# v11.net
KiCad netlist of a schematic drawn in EAGLE
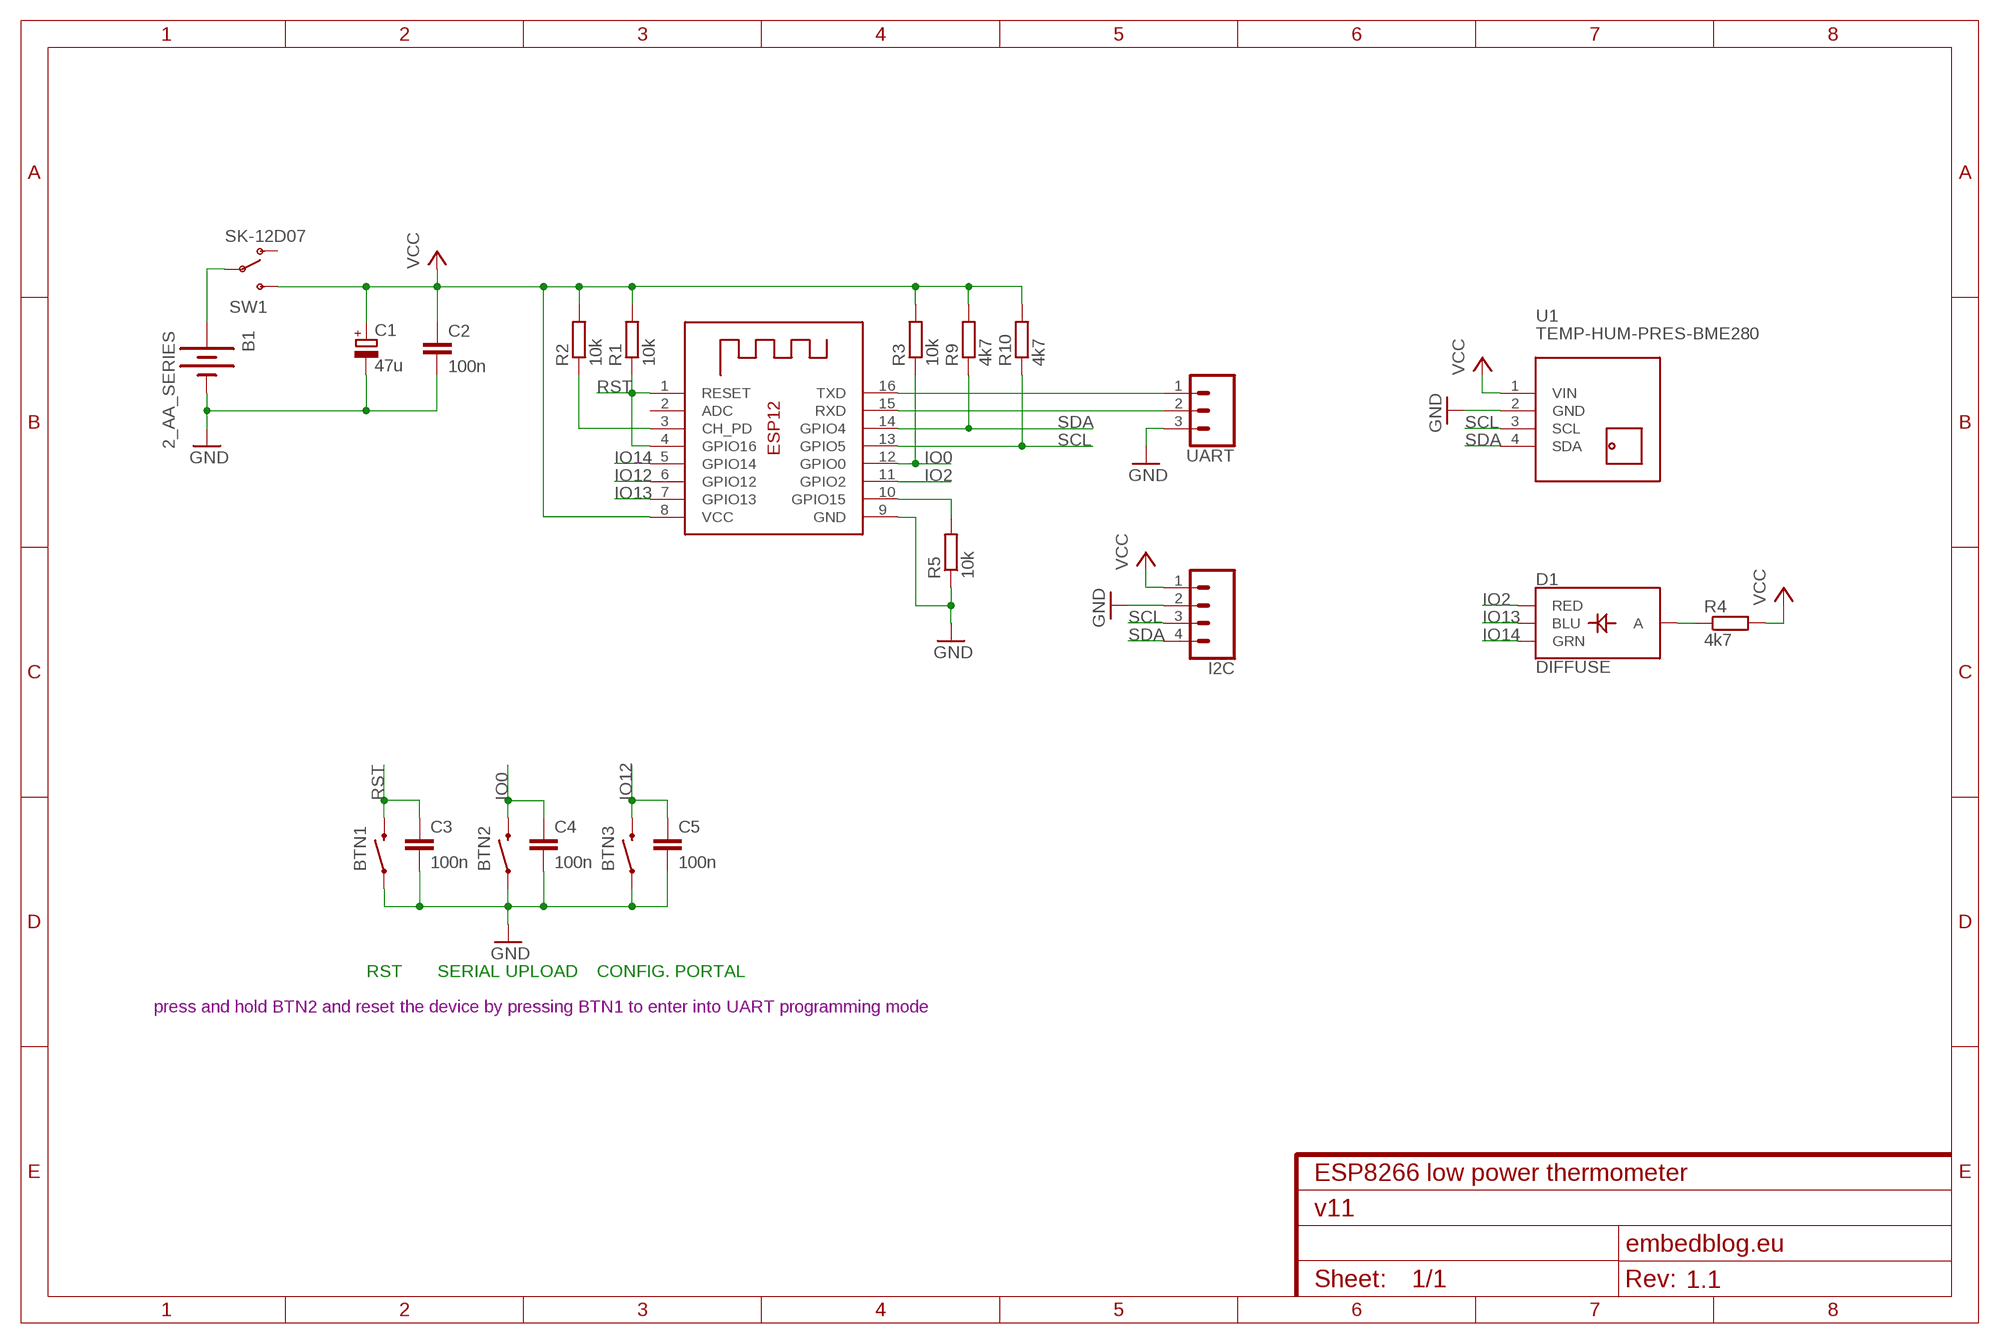
[diagram p0: schematic, sheet 1]

(export (version "E")
  (design (tool "Eeschema 10.0.6"))
  (components
    (comp (ref "B1")
      (value "2_AA_SERIES")
      (footprint "eagle-import:AA_HOLDER_BH-321-1P")
      (libsource (lib "eagle-import") (part "2_AA_SERIES"))
    )
    (comp (ref "BTN1")
      (value "MOMENTARY-SWITCH-SPST-PTH-6.0MM")
      (footprint "eagle-import:TACTILE_SWITCH_PTH_6.0MM")
      (libsource (lib "eagle-import") (part "MOMENTARY-SWITCH-SPST-PTH-6.0MM"))
    )
    (comp (ref "BTN2")
      (value "MOMENTARY-SWITCH-SPST-PTH-6.0MM")
      (footprint "eagle-import:TACTILE_SWITCH_PTH_6.0MM")
      (libsource (lib "eagle-import") (part "MOMENTARY-SWITCH-SPST-PTH-6.0MM"))
    )
    (comp (ref "BTN3")
      (value "MOMENTARY-SWITCH-SPST-PTH-6.0MM")
      (footprint "eagle-import:TACTILE_SWITCH_PTH_6.0MM")
      (libsource (lib "eagle-import") (part "MOMENTARY-SWITCH-SPST-PTH-6.0MM"))
    )
    (comp (ref "C1")
      (value "47u")
      (footprint "eagle-import:SMC_B")
      (libsource (lib "eagle-import") (part "CPOL-EUSMCB"))
    )
    (comp (ref "C2")
      (value "100n")
      (footprint "eagle-import:C1206")
      (libsource (lib "eagle-import") (part "C-EUC1206"))
    )
    (comp (ref "C3")
      (value "100n")
      (footprint "eagle-import:C1206")
      (libsource (lib "eagle-import") (part "C-EUC1206"))
    )
    (comp (ref "C4")
      (value "100n")
      (footprint "eagle-import:C1206")
      (libsource (lib "eagle-import") (part "C-EUC1206"))
    )
    (comp (ref "C5")
      (value "100n")
      (footprint "eagle-import:C1206")
      (libsource (lib "eagle-import") (part "C-EUC1206"))
    )
    (comp (ref "D1")
      (value "DIFFUSE")
      (footprint "eagle-import:LED-RGB-THRU")
      (libsource (lib "eagle-import") (part "LED-RGB-CADIFFUSE"))
    )
    (comp (ref "I2C")
      (value "CONN_04")
      (footprint "eagle-import:1X04")
      (libsource (lib "eagle-import") (part "CONN_04"))
    )
    (comp (ref "R1")
      (value "10k")
      (footprint "eagle-import:R1206")
      (libsource (lib "eagle-import") (part "R-EU_R1206"))
    )
    (comp (ref "R2")
      (value "10k")
      (footprint "eagle-import:R1206")
      (libsource (lib "eagle-import") (part "R-EU_R1206"))
    )
    (comp (ref "R3")
      (value "10k")
      (footprint "eagle-import:R1206")
      (libsource (lib "eagle-import") (part "R-EU_R1206"))
    )
    (comp (ref "R4")
      (value "4k7")
      (footprint "eagle-import:R1206")
      (libsource (lib "eagle-import") (part "R-EU_R1206"))
    )
    (comp (ref "R5")
      (value "10k")
      (footprint "eagle-import:R1206")
      (libsource (lib "eagle-import") (part "R-EU_R1206"))
    )
    (comp (ref "R9")
      (value "4k7")
      (footprint "eagle-import:R1206")
      (libsource (lib "eagle-import") (part "R-EU_R1206"))
    )
    (comp (ref "R10")
      (value "4k7")
      (footprint "eagle-import:R1206")
      (libsource (lib "eagle-import") (part "R-EU_R1206"))
    )
    (comp (ref "SW1")
      (value "SK-12D07")
      (footprint "eagle-import:SK12SWITCH")
      (libsource (lib "eagle-import") (part "SK-12D07"))
    )
    (comp (ref "U1")
      (value "TEMP-HUM-PRES-BME280")
      (footprint "eagle-import:TEMP-HUM-PRES-BME280")
      (libsource (lib "eagle-import") (part "TEMP-HUM-PRES-BME280"))
    )
    (comp (ref "UART")
      (value "455-1750-1-ND")
      (footprint "eagle-import:1X03")
      (libsource (lib "eagle-import") (part "CONN_03"))
    )
    (comp (ref "X1")
      (value "ESP-12")
      (footprint "eagle-import:ESP-12")
      (libsource (lib "eagle-import") (part "ESP-12"))
    )
  )
  (nets
    (net (code "1") (name "/IO0") (class "Default")
      (node (ref "BTN2") (pin "3") (pinfunction "2_3") (pintype "passive"))
      (node (ref "C4") (pin "1") (pinfunction "1_1") (pintype "passive"))
      (node (ref "R3") (pin "1") (pinfunction "1_1") (pintype "passive"))
      (node (ref "X1") (pin "12") (pinfunction "GPIO0_12") (pintype "bidirectional"))
    )
    (net (code "2") (name "/IO2") (class "Default")
      (node (ref "D1") (pin "1") (pinfunction "RED_1") (pintype "bidirectional"))
      (node (ref "X1") (pin "11") (pinfunction "GPIO2_11") (pintype "bidirectional"))
    )
    (net (code "3") (name "/IO12") (class "Default")
      (node (ref "BTN3") (pin "3") (pinfunction "2_3") (pintype "passive"))
      (node (ref "C5") (pin "1") (pinfunction "1_1") (pintype "passive"))
      (node (ref "X1") (pin "6") (pinfunction "GPIO12_6") (pintype "bidirectional"))
    )
    (net (code "4") (name "/IO13") (class "Default")
      (node (ref "D1") (pin "4") (pinfunction "BLU_4") (pintype "bidirectional"))
      (node (ref "X1") (pin "7") (pinfunction "GPIO13_7") (pintype "bidirectional"))
    )
    (net (code "5") (name "/IO14") (class "Default")
      (node (ref "D1") (pin "3") (pinfunction "GRN_3") (pintype "bidirectional"))
      (node (ref "X1") (pin "5") (pinfunction "GPIO14_5") (pintype "bidirectional"))
    )
    (net (code "6") (name "/RST") (class "Default")
      (node (ref "BTN1") (pin "3") (pinfunction "2_3") (pintype "passive"))
      (node (ref "C3") (pin "1") (pinfunction "1_1") (pintype "passive"))
      (node (ref "R1") (pin "1") (pinfunction "1_1") (pintype "passive"))
      (node (ref "X1") (pin "1") (pinfunction "RESET_1") (pintype "input"))
      (node (ref "X1") (pin "4") (pinfunction "GPIO16_4") (pintype "bidirectional"))
    )
    (net (code "7") (name "/SCL") (class "Default")
      (node (ref "I2C") (pin "3") (pinfunction "3_3") (pintype "passive"))
      (node (ref "R10") (pin "1") (pinfunction "1_1") (pintype "passive"))
      (node (ref "U1") (pin "3") (pinfunction "SCL_3") (pintype "bidirectional"))
      (node (ref "X1") (pin "13") (pinfunction "GPIO5_13") (pintype "bidirectional"))
    )
    (net (code "8") (name "/SDA") (class "Default")
      (node (ref "I2C") (pin "4") (pinfunction "4_4") (pintype "passive"))
      (node (ref "R9") (pin "1") (pinfunction "1_1") (pintype "passive"))
      (node (ref "U1") (pin "4") (pinfunction "SDA_4") (pintype "bidirectional"))
      (node (ref "X1") (pin "14") (pinfunction "GPIO4_14") (pintype "bidirectional"))
    )
    (net (code "9") (name "GND") (class "Default")
      (node (ref "B1") (pin "NEG") (pinfunction "-_NEG") (pintype "power_in"))
      (node (ref "BTN1") (pin "1") (pinfunction "1_1") (pintype "passive"))
      (node (ref "BTN2") (pin "1") (pinfunction "1_1") (pintype "passive"))
      (node (ref "BTN3") (pin "1") (pinfunction "1_1") (pintype "passive"))
      (node (ref "C1") (pin "-") (pinfunction "-_-") (pintype "passive"))
      (node (ref "C2") (pin "2") (pinfunction "2_2") (pintype "passive"))
      (node (ref "C3") (pin "2") (pinfunction "2_2") (pintype "passive"))
      (node (ref "C4") (pin "2") (pinfunction "2_2") (pintype "passive"))
      (node (ref "C5") (pin "2") (pinfunction "2_2") (pintype "passive"))
      (node (ref "I2C") (pin "2") (pinfunction "2_2") (pintype "passive"))
      (node (ref "R5") (pin "1") (pinfunction "1_1") (pintype "passive"))
      (node (ref "U1") (pin "2") (pinfunction "GND_2") (pintype "power_in"))
      (node (ref "UART") (pin "3") (pinfunction "3_3") (pintype "passive"))
      (node (ref "X1") (pin "9") (pinfunction "GND_9") (pintype "power_in"))
    )
    (net (code "10") (name "Net-(B1-+)") (class "Default")
      (node (ref "B1") (pin "POS") (pinfunction "+_POS") (pintype "power_in"))
      (node (ref "SW1") (pin "P2") (pinfunction "P_P2") (pintype "passive"))
    )
    (net (code "11") (name "Net-(D1-A)") (class "Default")
      (node (ref "D1") (pin "2") (pinfunction "A_2") (pintype "bidirectional"))
      (node (ref "R4") (pin "1") (pinfunction "1_1") (pintype "passive"))
    )
    (net (code "12") (name "Net-(X1-CH_PD)") (class "Default")
      (node (ref "R2") (pin "1") (pinfunction "1_1") (pintype "passive"))
      (node (ref "X1") (pin "3") (pinfunction "CH_PD_3") (pintype "input"))
    )
    (net (code "13") (name "Net-(X1-GPIO15)") (class "Default")
      (node (ref "R5") (pin "2") (pinfunction "2_2") (pintype "passive"))
      (node (ref "X1") (pin "10") (pinfunction "GPIO15_10") (pintype "bidirectional"))
    )
    (net (code "14") (name "Net-(X1-RXD)") (class "Default")
      (node (ref "UART") (pin "2") (pinfunction "2_2") (pintype "passive"))
      (node (ref "X1") (pin "15") (pinfunction "RXD_15") (pintype "input"))
    )
    (net (code "15") (name "Net-(X1-TXD)") (class "Default")
      (node (ref "UART") (pin "1") (pinfunction "1_1") (pintype "passive"))
      (node (ref "X1") (pin "16") (pinfunction "TXD_16") (pintype "output"))
    )
    (net (code "16") (name "VCC") (class "Default")
      (node (ref "C1") (pin "+") (pinfunction "+_+") (pintype "passive"))
      (node (ref "C2") (pin "1") (pinfunction "1_1") (pintype "passive"))
      (node (ref "I2C") (pin "1") (pinfunction "1_1") (pintype "passive"))
      (node (ref "R1") (pin "2") (pinfunction "2_2") (pintype "passive"))
      (node (ref "R10") (pin "2") (pinfunction "2_2") (pintype "passive"))
      (node (ref "R2") (pin "2") (pinfunction "2_2") (pintype "passive"))
      (node (ref "R3") (pin "2") (pinfunction "2_2") (pintype "passive"))
      (node (ref "R4") (pin "2") (pinfunction "2_2") (pintype "passive"))
      (node (ref "R9") (pin "2") (pinfunction "2_2") (pintype "passive"))
      (node (ref "SW1") (pin "IN") (pinfunction "S_IN") (pintype "passive"))
      (node (ref "U1") (pin "1") (pinfunction "VIN_1") (pintype "power_in"))
      (node (ref "X1") (pin "8") (pinfunction "VCC_8") (pintype "power_in"))
    )
    (net (code "17") (name "unconnected-(SW1-O-PadP1)") (class "Default")
      (node (ref "SW1") (pin "P1") (pinfunction "O_P1") (pintype "passive"))
    )
    (net (code "18") (name "unconnected-(X1-ADC-Pad2)") (class "Default")
      (node (ref "X1") (pin "2") (pinfunction "ADC_2") (pintype "passive"))
    )
  )
)
